# 4.net
KiCad netlist of a schematic drawn in Altium Designer
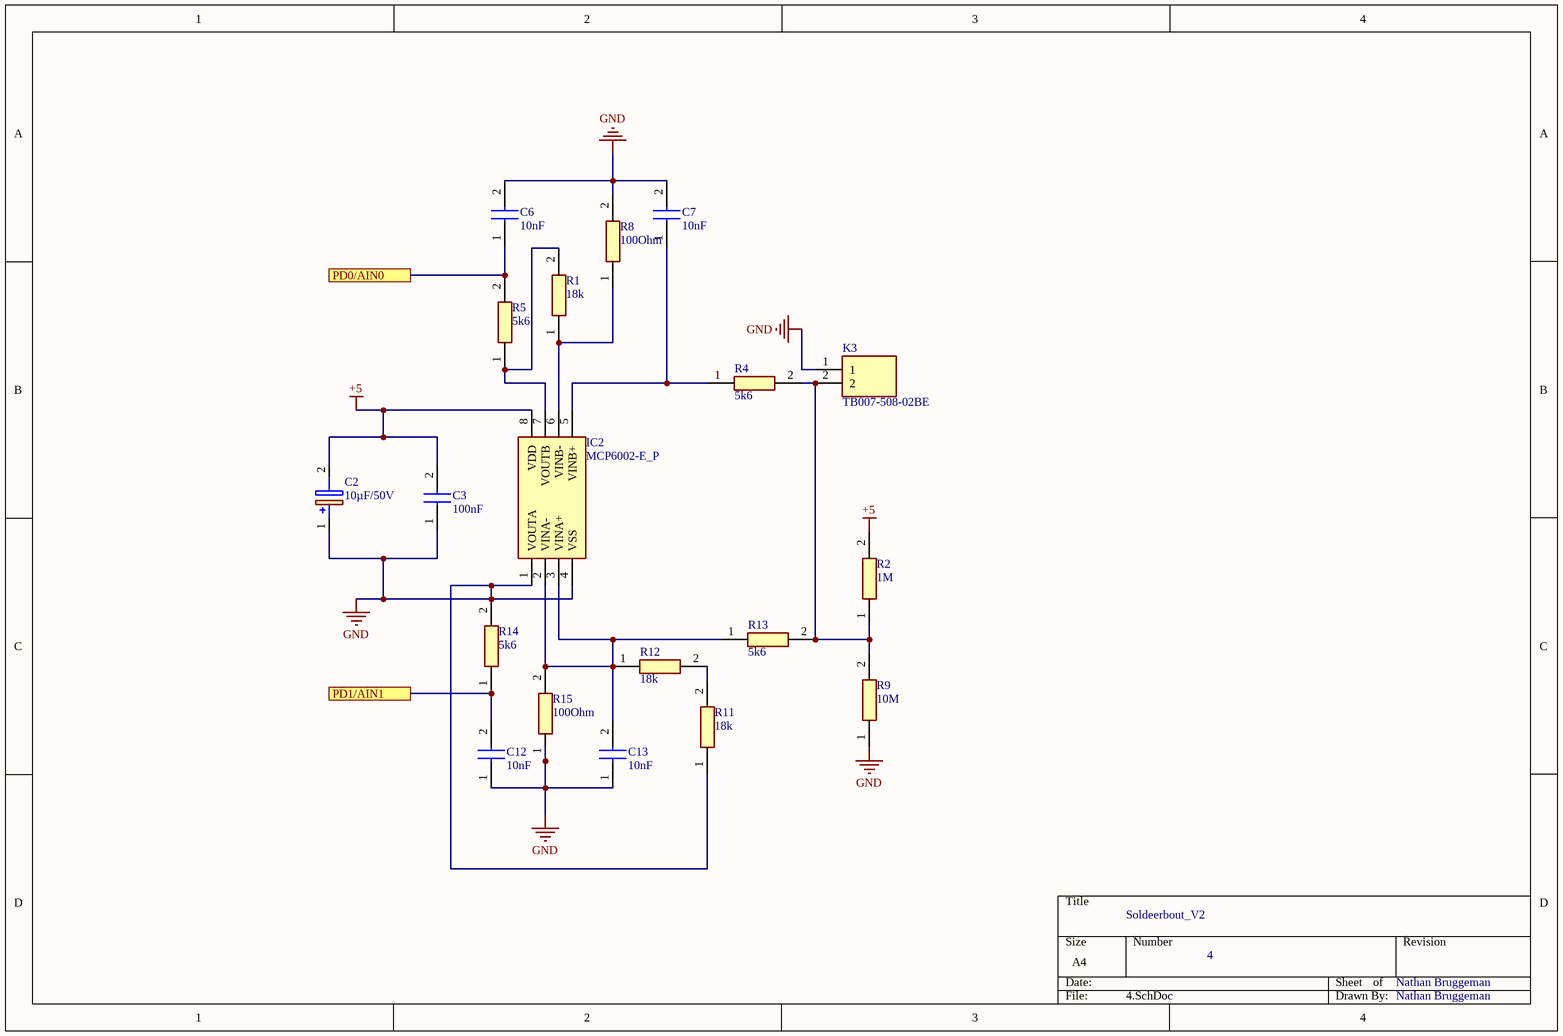
[diagram p0: 4.SchDoc]

(export (version "E")
  (design (tool "Eeschema 10.0.6"))
  (components
    (comp (ref "C2")
      (value "10µF/50V")
      (footprint "CAPPRD200W55D500H1200")
      (description "Capacitor Polarised")
      (fields
        (field (name "MOUSER2 PART NUMBER") "667-ECA-1HM100")
        (field (name "MANUFACTURER_PART_NUMBER") "ECA-1HM100")
      )
      (libsource (lib "Condensator_10µF_V2") (part "ECA-1HM100"))
    )
    (comp (ref "C3")
      (value "100nF")
      (footprint "0805")
      (description "Capacitor")
      (fields (field (name "MANUFACTURER_PART_NUMBER") "C0805C301G5GACTU"))
      (libsource (lib "Condensator_0805") (part "C0805C301G5GACTU"))
    )
    (comp (ref "C6")
      (value "10nF")
      (footprint "0805")
      (description "Capacitor")
      (fields (field (name "MANUFACTURER_PART_NUMBER") "C0805C301G5GACTU"))
      (libsource (lib "Condensator_0805") (part "C0805C301G5GACTU"))
    )
    (comp (ref "C7")
      (value "10nF")
      (footprint "0805")
      (description "Capacitor")
      (fields (field (name "MANUFACTURER_PART_NUMBER") "C0805C301G5GACTU"))
      (libsource (lib "Condensator_0805") (part "C0805C301G5GACTU"))
    )
    (comp (ref "C12")
      (value "10nF")
      (footprint "0805")
      (description "Capacitor")
      (fields (field (name "MANUFACTURER_PART_NUMBER") "C0805C301G5GACTU"))
      (libsource (lib "Condensator_0805") (part "C0805C301G5GACTU"))
    )
    (comp (ref "C13")
      (value "10nF")
      (footprint "0805")
      (description "Capacitor")
      (fields (field (name "MANUFACTURER_PART_NUMBER") "C0805C301G5GACTU"))
      (libsource (lib "Condensator_0805") (part "C0805C301G5GACTU"))
    )
    (comp (ref "IC2")
      (value "MCP6002-E_P")
      (footprint "DIP781W56P254L950H533Q8N")
      (description "Integrated Circuit")
      (fields
        (field (name "MOUSER2 PART NUMBER") "579-MCP6002-E/P")
        (field (name "MANUFACTURER_PART_NUMBER") "MCP6002-E/P")
      )
      (libsource (lib "IC2_V2") (part "MCP6002-E_P"))
    )
    (comp (ref "K3")
      (value "TB007-508-02BE")
      (footprint "TB00750802BE")
      (description "Connector")
      (fields (field (name "MOUSER2 PART NUMBER") "490-TB007-508-02BE"))
      (libsource (lib "K1_K2_K3_K8") (part "TB007-508-02BE"))
    )
    (comp (ref "R1")
      (value "18k")
      (footprint "0805")
      (description "Resistor")
      (fields (field (name "MANUFACTURER_PART_NUMBER") "CFN0805-FZ-R030ELF"))
      (libsource (lib "Weerstand_0805") (part "CFN0805-FZ-R030ELF"))
    )
    (comp (ref "R2")
      (value "1M")
      (footprint "0805")
      (description "Resistor")
      (fields (field (name "MANUFACTURER_PART_NUMBER") "CFN0805-FZ-R030ELF"))
      (libsource (lib "Weerstand_0805") (part "CFN0805-FZ-R030ELF"))
    )
    (comp (ref "R4")
      (value "5k6")
      (footprint "0805")
      (description "Resistor")
      (fields (field (name "MANUFACTURER_PART_NUMBER") "CFN0805-FZ-R030ELF"))
      (libsource (lib "") (part "CFN0805-FZ-R030ELF_1"))
    )
    (comp (ref "R5")
      (value "5k6")
      (footprint "0805")
      (description "Resistor")
      (fields (field (name "MANUFACTURER_PART_NUMBER") "CFN0805-FZ-R030ELF"))
      (libsource (lib "Weerstand_0805") (part "CFN0805-FZ-R030ELF"))
    )
    (comp (ref "R8")
      (value "100Ohm")
      (footprint "0805")
      (description "Resistor")
      (fields (field (name "MANUFACTURER_PART_NUMBER") "CFN0805-FZ-R030ELF"))
      (libsource (lib "Weerstand_0805") (part "CFN0805-FZ-R030ELF"))
    )
    (comp (ref "R9")
      (value "10M")
      (footprint "0805")
      (description "Resistor")
      (fields (field (name "MANUFACTURER_PART_NUMBER") "CFN0805-FZ-R030ELF"))
      (libsource (lib "Weerstand_0805") (part "CFN0805-FZ-R030ELF"))
    )
    (comp (ref "R11")
      (value "18k")
      (footprint "0805")
      (description "Resistor")
      (fields (field (name "MANUFACTURER_PART_NUMBER") "CFN0805-FZ-R030ELF"))
      (libsource (lib "Weerstand_0805") (part "CFN0805-FZ-R030ELF"))
    )
    (comp (ref "R12")
      (value "18k")
      (footprint "0805")
      (description "Resistor")
      (fields (field (name "MANUFACTURER_PART_NUMBER") "CFN0805-FZ-R030ELF"))
      (libsource (lib "") (part "CFN0805-FZ-R030ELF_1"))
    )
    (comp (ref "R13")
      (value "5k6")
      (footprint "0805")
      (description "Resistor")
      (fields (field (name "MANUFACTURER_PART_NUMBER") "CFN0805-FZ-R030ELF"))
      (libsource (lib "") (part "CFN0805-FZ-R030ELF_1"))
    )
    (comp (ref "R14")
      (value "5k6")
      (footprint "0805")
      (description "Resistor")
      (fields (field (name "MANUFACTURER_PART_NUMBER") "CFN0805-FZ-R030ELF"))
      (libsource (lib "Weerstand_0805") (part "CFN0805-FZ-R030ELF"))
    )
    (comp (ref "R15")
      (value "100Ohm")
      (footprint "0805")
      (description "Resistor")
      (fields (field (name "MANUFACTURER_PART_NUMBER") "CFN0805-FZ-R030ELF"))
      (libsource (lib "Weerstand_0805") (part "CFN0805-FZ-R030ELF"))
    )
  )
  (nets
    (net (code "1") (name "+5") (class "Default")
      (node (ref "C2") (pin "2") (pinfunction "-_2") (pintype "passive"))
      (node (ref "C3") (pin "2") (pinfunction "2_2") (pintype "passive"))
      (node (ref "IC2") (pin "8") (pinfunction "VDD_8") (pintype "passive"))
      (node (ref "R2") (pin "2") (pinfunction "2_2") (pintype "passive"))
    )
    (net (code "2") (name "/PD0{slash}AIN0") (class "Default")
      (node (ref "C6") (pin "1") (pinfunction "1_1") (pintype "passive"))
      (node (ref "R5") (pin "2") (pinfunction "2_2") (pintype "passive"))
    )
    (net (code "3") (name "/PD1{slash}AIN1") (class "Default")
      (node (ref "C12") (pin "2") (pinfunction "2_2") (pintype "passive"))
      (node (ref "R14") (pin "1") (pinfunction "1_1") (pintype "passive"))
    )
    (net (code "4") (name "GND") (class "Default")
      (node (ref "C12") (pin "1") (pinfunction "1_1") (pintype "passive"))
      (node (ref "C13") (pin "1") (pinfunction "1_1") (pintype "passive"))
      (node (ref "C2") (pin "1") (pinfunction "+_1") (pintype "passive"))
      (node (ref "C3") (pin "1") (pinfunction "1_1") (pintype "passive"))
      (node (ref "C6") (pin "2") (pinfunction "2_2") (pintype "passive"))
      (node (ref "C7") (pin "2") (pinfunction "2_2") (pintype "passive"))
      (node (ref "IC2") (pin "1") (pinfunction "VOUTA_1") (pintype "passive"))
      (node (ref "IC2") (pin "4") (pinfunction "VSS_4") (pintype "passive"))
      (node (ref "K3") (pin "1") (pinfunction "1_1") (pintype "passive"))
      (node (ref "R11") (pin "1") (pinfunction "1_1") (pintype "passive"))
      (node (ref "R14") (pin "2") (pinfunction "2_2") (pintype "passive"))
      (node (ref "R15") (pin "1") (pinfunction "1_1") (pintype "passive"))
      (node (ref "R8") (pin "2") (pinfunction "2_2") (pintype "passive"))
      (node (ref "R9") (pin "1") (pinfunction "1_1") (pintype "passive"))
    )
    (net (code "5") (name "Net-(IC2-VINA+)") (class "Default")
      (node (ref "C13") (pin "2") (pinfunction "2_2") (pintype "passive"))
      (node (ref "IC2") (pin "2") (pinfunction "VINA-_2") (pintype "passive"))
      (node (ref "IC2") (pin "3") (pinfunction "VINA+_3") (pintype "passive"))
      (node (ref "R12") (pin "1") (pinfunction "1_1") (pintype "passive"))
      (node (ref "R13") (pin "1") (pinfunction "1_1") (pintype "passive"))
      (node (ref "R15") (pin "2") (pinfunction "2_2") (pintype "passive"))
    )
    (net (code "6") (name "Net-(IC2-VINB+)") (class "Default")
      (node (ref "C7") (pin "1") (pinfunction "1_1") (pintype "passive"))
      (node (ref "IC2") (pin "5") (pinfunction "VINB+_5") (pintype "passive"))
      (node (ref "R4") (pin "1") (pinfunction "1_1") (pintype "passive"))
    )
    (net (code "7") (name "Net-(IC2-VINB-)") (class "Default")
      (node (ref "IC2") (pin "6") (pinfunction "VINB-_6") (pintype "passive"))
      (node (ref "R1") (pin "1") (pinfunction "1_1") (pintype "passive"))
      (node (ref "R8") (pin "1") (pinfunction "1_1") (pintype "passive"))
    )
    (net (code "8") (name "Net-(IC2-VOUTB)") (class "Default")
      (node (ref "IC2") (pin "7") (pinfunction "VOUTB_7") (pintype "passive"))
      (node (ref "R1") (pin "2") (pinfunction "2_2") (pintype "passive"))
      (node (ref "R5") (pin "1") (pinfunction "1_1") (pintype "passive"))
    )
    (net (code "9") (name "Net-(K3-Pad2)") (class "Default")
      (node (ref "K3") (pin "2") (pinfunction "2_2") (pintype "passive"))
      (node (ref "R13") (pin "2") (pinfunction "2_2") (pintype "passive"))
      (node (ref "R2") (pin "1") (pinfunction "1_1") (pintype "passive"))
      (node (ref "R4") (pin "2") (pinfunction "2_2") (pintype "passive"))
      (node (ref "R9") (pin "2") (pinfunction "2_2") (pintype "passive"))
    )
    (net (code "10") (name "Net-(R11-Pad2)") (class "Default")
      (node (ref "R11") (pin "2") (pinfunction "2_2") (pintype "passive"))
      (node (ref "R12") (pin "2") (pinfunction "2_2") (pintype "passive"))
    )
  )
)
